# connect.net
KiCad netlist of a schematic drawn in Altium Designer
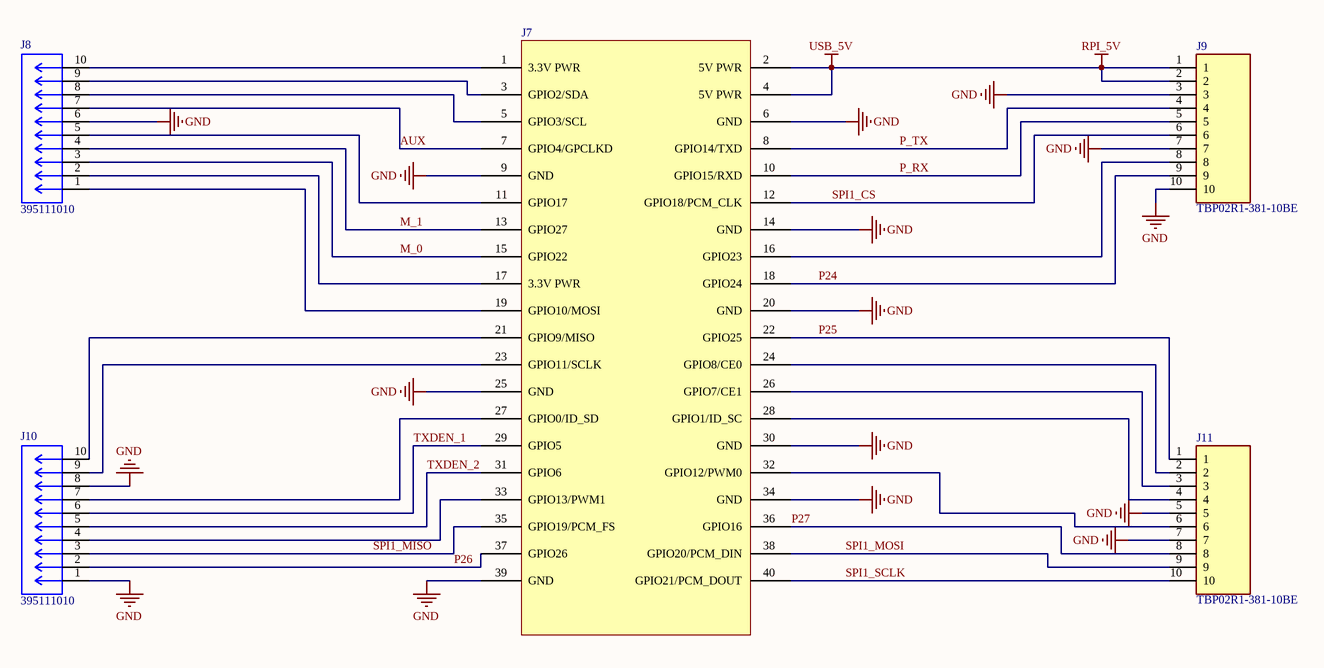
[diagram p0: connect.SchDoc]

(export (version "E")
  (design (tool "Eeschema 10.0.6"))
  (components
    (comp (ref "J7")
      (value "~")
      (footprint "GPIO_INTERFACE")
      (description "RASPBERRY_INTERFACE")
      (libsource (lib "VIETTIEN") (part "RASPBERRY_INTERFACE"))
    )
    (comp (ref "J8")
      (value "395111010")
      (footprint "CONN_SD-39511-001_10P_MOL")
      (description "Pluggable Terminal Blocks 3.81MM EURO HEADER V EADER VERT BLK 10CKT")
      (fields (field (name "MF") "Molex"))
      (libsource (lib "VIETTIEN") (part "395111010"))
    )
    (comp (ref "J9")
      (value "TBP02R1-381-10BE")
      (footprint "CUI_TBP02R1-381-10BE")
      (fields (field (name "MF") "Same Sky"))
      (libsource (lib "VIETTIEN") (part "TBP02R1-381-10BE"))
    )
    (comp (ref "J10")
      (value "395111010")
      (footprint "CONN_SD-39511-001_10P_MOL")
      (description "Pluggable Terminal Blocks 3.81MM EURO HEADER V EADER VERT BLK 10CKT")
      (fields (field (name "MF") "Molex"))
      (libsource (lib "VIETTIEN") (part "395111010"))
    )
    (comp (ref "J11")
      (value "TBP02R1-381-10BE")
      (footprint "CUI_TBP02R1-381-10BE")
      (fields (field (name "MF") "Same Sky"))
      (libsource (lib "VIETTIEN") (part "TBP02R1-381-10BE"))
    )
  )
  (nets
    (net (code "1") (name "/AUX") (class "Default")
      (node (ref "J7") (pin "7") (pinfunction "GPIO4/GPCLKD_7") (pintype "passive"))
      (node (ref "J8") (pin "7") (pinfunction "7_7") (pintype "passive"))
    )
    (net (code "2") (name "/M_0") (class "Default")
      (node (ref "J7") (pin "15") (pinfunction "GPIO22_15") (pintype "passive"))
      (node (ref "J8") (pin "3") (pinfunction "3_3") (pintype "passive"))
    )
    (net (code "3") (name "/M_1") (class "Default")
      (node (ref "J7") (pin "13") (pinfunction "GPIO27_13") (pintype "passive"))
      (node (ref "J8") (pin "4") (pinfunction "4_4") (pintype "passive"))
    )
    (net (code "4") (name "/P24") (class "Default")
      (node (ref "J7") (pin "18") (pinfunction "GPIO24_18") (pintype "passive"))
      (node (ref "J9") (pin "9") (pinfunction "9_9") (pintype "passive"))
    )
    (net (code "5") (name "/P25") (class "Default")
      (node (ref "J11") (pin "1") (pinfunction "1_1") (pintype "passive"))
      (node (ref "J7") (pin "22") (pinfunction "GPIO25_22") (pintype "passive"))
    )
    (net (code "6") (name "/P26") (class "Default")
      (node (ref "J10") (pin "2") (pinfunction "2_2") (pintype "passive"))
      (node (ref "J7") (pin "37") (pinfunction "GPIO26_37") (pintype "passive"))
    )
    (net (code "7") (name "/P27") (class "Default")
      (node (ref "J11") (pin "8") (pinfunction "8_8") (pintype "passive"))
      (node (ref "J7") (pin "36") (pinfunction "GPIO16_36") (pintype "passive"))
    )
    (net (code "8") (name "/P_RX") (class "Default")
      (node (ref "J7") (pin "10") (pinfunction "GPIO15/RXD_10") (pintype "passive"))
      (node (ref "J9") (pin "5") (pinfunction "5_5") (pintype "passive"))
    )
    (net (code "9") (name "/P_TX") (class "Default")
      (node (ref "J7") (pin "8") (pinfunction "GPIO14/TXD_8") (pintype "passive"))
      (node (ref "J9") (pin "4") (pinfunction "4_4") (pintype "passive"))
    )
    (net (code "10") (name "/SPI1_CS") (class "Default")
      (node (ref "J7") (pin "12") (pinfunction "GPIO18/PCM_CLK_12") (pintype "passive"))
      (node (ref "J9") (pin "6") (pinfunction "6_6") (pintype "passive"))
    )
    (net (code "11") (name "/SPI1_MISO") (class "Default")
      (node (ref "J10") (pin "3") (pinfunction "3_3") (pintype "passive"))
      (node (ref "J7") (pin "35") (pinfunction "GPIO19/PCM_FS_35") (pintype "passive"))
    )
    (net (code "12") (name "/SPI1_MOSI") (class "Default")
      (node (ref "J11") (pin "9") (pinfunction "9_9") (pintype "passive"))
      (node (ref "J7") (pin "38") (pinfunction "GPIO20/PCM_DIN_38") (pintype "passive"))
    )
    (net (code "13") (name "/SPI1_SCLK") (class "Default")
      (node (ref "J11") (pin "10") (pinfunction "10_10") (pintype "passive"))
      (node (ref "J7") (pin "40") (pinfunction "GPIO21/PCM_DOUT_40") (pintype "passive"))
    )
    (net (code "14") (name "/TXDEN_1") (class "Default")
      (node (ref "J10") (pin "6") (pinfunction "6_6") (pintype "passive"))
      (node (ref "J7") (pin "29") (pinfunction "GPIO5_29") (pintype "passive"))
    )
    (net (code "15") (name "/TXDEN_2") (class "Default")
      (node (ref "J10") (pin "5") (pinfunction "5_5") (pintype "passive"))
      (node (ref "J7") (pin "31") (pinfunction "GPIO6_31") (pintype "passive"))
    )
    (net (code "16") (name "GND") (class "Default")
      (node (ref "J10") (pin "1") (pinfunction "1_1") (pintype "passive"))
      (node (ref "J10") (pin "8") (pinfunction "8_8") (pintype "passive"))
      (node (ref "J11") (pin "5") (pinfunction "5_5") (pintype "passive"))
      (node (ref "J11") (pin "7") (pinfunction "7_7") (pintype "passive"))
      (node (ref "J7") (pin "14") (pinfunction "GND_14") (pintype "passive"))
      (node (ref "J7") (pin "20") (pinfunction "GND_20") (pintype "passive"))
      (node (ref "J7") (pin "25") (pinfunction "GND_25") (pintype "passive"))
      (node (ref "J7") (pin "30") (pinfunction "GND_30") (pintype "passive"))
      (node (ref "J7") (pin "34") (pinfunction "GND_34") (pintype "passive"))
      (node (ref "J7") (pin "39") (pinfunction "GND_39") (pintype "passive"))
      (node (ref "J7") (pin "6") (pinfunction "GND_6") (pintype "passive"))
      (node (ref "J7") (pin "9") (pinfunction "GND_9") (pintype "passive"))
      (node (ref "J8") (pin "6") (pinfunction "6_6") (pintype "passive"))
      (node (ref "J9") (pin "10") (pinfunction "10_10") (pintype "passive"))
      (node (ref "J9") (pin "3") (pinfunction "3_3") (pintype "passive"))
      (node (ref "J9") (pin "7") (pinfunction "7_7") (pintype "passive"))
    )
    (net (code "17") (name "Net-(J7-3.3V_PWR-Pad1)") (class "Default")
      (node (ref "J7") (pin "1") (pinfunction "3.3V_PWR_1") (pintype "passive"))
      (node (ref "J8") (pin "10") (pinfunction "10_10") (pintype "passive"))
    )
    (net (code "18") (name "Net-(J7-3.3V_PWR-Pad17)") (class "Default")
      (node (ref "J7") (pin "17") (pinfunction "3.3V_PWR_17") (pintype "passive"))
      (node (ref "J8") (pin "2") (pinfunction "2_2") (pintype "passive"))
    )
    (net (code "19") (name "Net-(J7-GPIO0{slash}ID_SD)") (class "Default")
      (node (ref "J10") (pin "7") (pinfunction "7_7") (pintype "passive"))
      (node (ref "J7") (pin "27") (pinfunction "GPIO0/ID_SD_27") (pintype "passive"))
    )
    (net (code "20") (name "Net-(J7-GPIO1{slash}ID_SC)") (class "Default")
      (node (ref "J11") (pin "4") (pinfunction "4_4") (pintype "passive"))
      (node (ref "J7") (pin "28") (pinfunction "GPIO1/ID_SC_28") (pintype "passive"))
    )
    (net (code "21") (name "Net-(J7-GPIO2{slash}SDA)") (class "Default")
      (node (ref "J7") (pin "3") (pinfunction "GPIO2/SDA_3") (pintype "passive"))
      (node (ref "J8") (pin "9") (pinfunction "9_9") (pintype "passive"))
    )
    (net (code "22") (name "Net-(J7-GPIO3{slash}SCL)") (class "Default")
      (node (ref "J7") (pin "5") (pinfunction "GPIO3/SCL_5") (pintype "passive"))
      (node (ref "J8") (pin "8") (pinfunction "8_8") (pintype "passive"))
    )
    (net (code "23") (name "Net-(J7-GPIO7{slash}CE1)") (class "Default")
      (node (ref "J11") (pin "3") (pinfunction "3_3") (pintype "passive"))
      (node (ref "J7") (pin "26") (pinfunction "GPIO7/CE1_26") (pintype "passive"))
    )
    (net (code "24") (name "Net-(J7-GPIO8{slash}CE0)") (class "Default")
      (node (ref "J11") (pin "2") (pinfunction "2_2") (pintype "passive"))
      (node (ref "J7") (pin "24") (pinfunction "GPIO8/CE0_24") (pintype "passive"))
    )
    (net (code "25") (name "Net-(J7-GPIO9{slash}MISO)") (class "Default")
      (node (ref "J10") (pin "10") (pinfunction "10_10") (pintype "passive"))
      (node (ref "J7") (pin "21") (pinfunction "GPIO9/MISO_21") (pintype "passive"))
    )
    (net (code "26") (name "Net-(J7-GPIO10{slash}MOSI)") (class "Default")
      (node (ref "J7") (pin "19") (pinfunction "GPIO10/MOSI_19") (pintype "passive"))
      (node (ref "J8") (pin "1") (pinfunction "1_1") (pintype "passive"))
    )
    (net (code "27") (name "Net-(J7-GPIO11{slash}SCLK)") (class "Default")
      (node (ref "J10") (pin "9") (pinfunction "9_9") (pintype "passive"))
      (node (ref "J7") (pin "23") (pinfunction "GPIO11/SCLK_23") (pintype "passive"))
    )
    (net (code "28") (name "Net-(J7-GPIO12{slash}PWM0)") (class "Default")
      (node (ref "J11") (pin "6") (pinfunction "6_6") (pintype "passive"))
      (node (ref "J7") (pin "32") (pinfunction "GPIO12/PWM0_32") (pintype "passive"))
    )
    (net (code "29") (name "Net-(J7-GPIO13{slash}PWM1)") (class "Default")
      (node (ref "J10") (pin "4") (pinfunction "4_4") (pintype "passive"))
      (node (ref "J7") (pin "33") (pinfunction "GPIO13/PWM1_33") (pintype "passive"))
    )
    (net (code "30") (name "Net-(J7-GPIO17)") (class "Default")
      (node (ref "J7") (pin "11") (pinfunction "GPIO17_11") (pintype "passive"))
      (node (ref "J8") (pin "5") (pinfunction "5_5") (pintype "passive"))
    )
    (net (code "31") (name "Net-(J7-GPIO23)") (class "Default")
      (node (ref "J7") (pin "16") (pinfunction "GPIO23_16") (pintype "passive"))
      (node (ref "J9") (pin "8") (pinfunction "8_8") (pintype "passive"))
    )
    (net (code "32") (name "RPI_5V") (class "Default")
      (node (ref "J7") (pin "2") (pinfunction "5V_PWR_2") (pintype "passive"))
      (node (ref "J7") (pin "4") (pinfunction "5V_PWR_4") (pintype "passive"))
      (node (ref "J9") (pin "1") (pinfunction "1_1") (pintype "passive"))
      (node (ref "J9") (pin "2") (pinfunction "2_2") (pintype "passive"))
    )
  )
)
